# others.net
KiCad netlist of a schematic drawn in Altium Designer
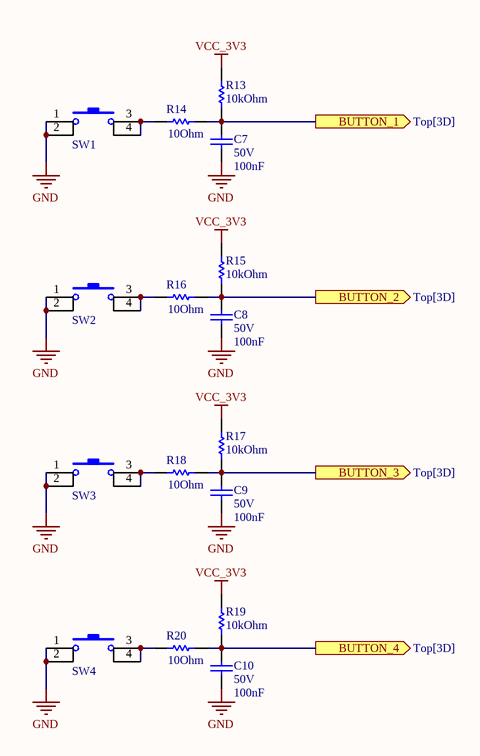
[diagram p0: others.SchDoc]

(export (version "E")
  (design (tool "Eeschema 10.0.6"))
  (components
    (comp (ref "C7")
      (value "~")
      (footprint "CAP_0603_High_density")
      (description "Generic Ceramic Capacitor SMD")
      (fields
        (field (name "TOLERANCE") "10%")
        (field (name "VOLTAGE") "50V")
        (field (name "CAPACITANCE") "100nF")
      )
      (libsource (lib "altium_conclusive_library") (part "Capacitor SMD"))
    )
    (comp (ref "C8")
      (value "~")
      (footprint "CAP_0603_High_density")
      (description "Generic Ceramic Capacitor SMD")
      (fields
        (field (name "TOLERANCE") "10%")
        (field (name "VOLTAGE") "50V")
        (field (name "CAPACITANCE") "100nF")
      )
      (libsource (lib "altium_conclusive_library") (part "Capacitor SMD"))
    )
    (comp (ref "C9")
      (value "~")
      (footprint "CAP_0603_High_density")
      (description "Generic Ceramic Capacitor SMD")
      (fields
        (field (name "TOLERANCE") "10%")
        (field (name "VOLTAGE") "50V")
        (field (name "CAPACITANCE") "100nF")
      )
      (libsource (lib "altium_conclusive_library") (part "Capacitor SMD"))
    )
    (comp (ref "C10")
      (value "~")
      (footprint "CAP_0603_High_density")
      (description "Generic Ceramic Capacitor SMD")
      (fields
        (field (name "TOLERANCE") "10%")
        (field (name "VOLTAGE") "50V")
        (field (name "CAPACITANCE") "100nF")
      )
      (libsource (lib "altium_conclusive_library") (part "Capacitor SMD"))
    )
    (comp (ref "R13")
      (value "0603 10kOhm 1%")
      (footprint "RES_0603")
      (description "Generic Resistor SMD")
      (fields (field (name "RESISTANCE") "10kOhm"))
      (libsource (lib "MY_LIB") (part "Resistor SMD_1"))
    )
    (comp (ref "R14")
      (value "0603 10Ohm 1%")
      (footprint "RES_0603")
      (description "Generic Resistor SMD")
      (fields (field (name "RESISTANCE") "10Ohm"))
      (libsource (lib "MY_LIB") (part "Resistor SMD_1"))
    )
    (comp (ref "R15")
      (value "0603 10kOhm 1%")
      (footprint "RES_0603")
      (description "Generic Resistor SMD")
      (fields (field (name "RESISTANCE") "10kOhm"))
      (libsource (lib "MY_LIB") (part "Resistor SMD_1"))
    )
    (comp (ref "R16")
      (value "0603 10Ohm 1%")
      (footprint "RES_0603")
      (description "Generic Resistor SMD")
      (fields (field (name "RESISTANCE") "10Ohm"))
      (libsource (lib "MY_LIB") (part "Resistor SMD_1"))
    )
    (comp (ref "R17")
      (value "0603 10kOhm 1%")
      (footprint "RES_0603")
      (description "Generic Resistor SMD")
      (fields (field (name "RESISTANCE") "10kOhm"))
      (libsource (lib "MY_LIB") (part "Resistor SMD_1"))
    )
    (comp (ref "R18")
      (value "0603 10Ohm 1%")
      (footprint "RES_0603")
      (description "Generic Resistor SMD")
      (fields (field (name "RESISTANCE") "10Ohm"))
      (libsource (lib "MY_LIB") (part "Resistor SMD_1"))
    )
    (comp (ref "R19")
      (value "0603 10kOhm 1%")
      (footprint "RES_0603")
      (description "Generic Resistor SMD")
      (fields (field (name "RESISTANCE") "10kOhm"))
      (libsource (lib "MY_LIB") (part "Resistor SMD_1"))
    )
    (comp (ref "R20")
      (value "0603 10Ohm 1%")
      (footprint "RES_0603")
      (description "Generic Resistor SMD")
      (fields (field (name "RESISTANCE") "10Ohm"))
      (libsource (lib "MY_LIB") (part "Resistor SMD_1"))
    )
    (comp (ref "SW1")
      (value "SWITCH SMD")
      (footprint "B3FS-1010")
      (description "SMD SWITCH B3FS-1010")
      (libsource (lib "MY_LIB") (part "B3FS-1010"))
    )
    (comp (ref "SW2")
      (value "SWITCH SMD")
      (footprint "B3FS-1010")
      (description "SMD SWITCH B3FS-1010")
      (libsource (lib "MY_LIB") (part "B3FS-1010"))
    )
    (comp (ref "SW3")
      (value "SWITCH SMD")
      (footprint "B3FS-1010")
      (description "SMD SWITCH B3FS-1010")
      (libsource (lib "MY_LIB") (part "B3FS-1010"))
    )
    (comp (ref "SW4")
      (value "SWITCH SMD")
      (footprint "B3FS-1010")
      (description "SMD SWITCH B3FS-1010")
      (libsource (lib "MY_LIB") (part "B3FS-1010"))
    )
  )
  (nets
    (net (code "1") (name "/BUTTON_1") (class "Default")
      (node (ref "C7") (pin "1") (pinfunction "1_1") (pintype "passive"))
      (node (ref "R13") (pin "2") (pinfunction "2_2") (pintype "passive"))
      (node (ref "R14") (pin "2") (pinfunction "2_2") (pintype "passive"))
    )
    (net (code "2") (name "/BUTTON_2") (class "Default")
      (node (ref "C8") (pin "1") (pinfunction "1_1") (pintype "passive"))
      (node (ref "R15") (pin "2") (pinfunction "2_2") (pintype "passive"))
      (node (ref "R16") (pin "2") (pinfunction "2_2") (pintype "passive"))
    )
    (net (code "3") (name "/BUTTON_3") (class "Default")
      (node (ref "C9") (pin "1") (pinfunction "1_1") (pintype "passive"))
      (node (ref "R17") (pin "2") (pinfunction "2_2") (pintype "passive"))
      (node (ref "R18") (pin "2") (pinfunction "2_2") (pintype "passive"))
    )
    (net (code "4") (name "/BUTTON_4") (class "Default")
      (node (ref "C10") (pin "1") (pinfunction "1_1") (pintype "passive"))
      (node (ref "R19") (pin "2") (pinfunction "2_2") (pintype "passive"))
      (node (ref "R20") (pin "2") (pinfunction "2_2") (pintype "passive"))
    )
    (net (code "5") (name "GND") (class "Default")
      (node (ref "C10") (pin "2") (pinfunction "2_2") (pintype "passive"))
      (node (ref "C7") (pin "2") (pinfunction "2_2") (pintype "passive"))
      (node (ref "C8") (pin "2") (pinfunction "2_2") (pintype "passive"))
      (node (ref "C9") (pin "2") (pinfunction "2_2") (pintype "passive"))
      (node (ref "SW1") (pin "1") (pinfunction "1_1") (pintype "passive"))
      (node (ref "SW1") (pin "2") (pinfunction "2_2") (pintype "passive"))
      (node (ref "SW2") (pin "1") (pinfunction "1_1") (pintype "passive"))
      (node (ref "SW2") (pin "2") (pinfunction "2_2") (pintype "passive"))
      (node (ref "SW3") (pin "1") (pinfunction "1_1") (pintype "passive"))
      (node (ref "SW3") (pin "2") (pinfunction "2_2") (pintype "passive"))
      (node (ref "SW4") (pin "1") (pinfunction "1_1") (pintype "passive"))
      (node (ref "SW4") (pin "2") (pinfunction "2_2") (pintype "passive"))
    )
    (net (code "6") (name "Net-(R14-Pad1)") (class "Default")
      (node (ref "R14") (pin "1") (pinfunction "1_1") (pintype "passive"))
      (node (ref "SW1") (pin "3") (pinfunction "3_3") (pintype "passive"))
      (node (ref "SW1") (pin "4") (pinfunction "4_4") (pintype "passive"))
    )
    (net (code "7") (name "Net-(R16-Pad1)") (class "Default")
      (node (ref "R16") (pin "1") (pinfunction "1_1") (pintype "passive"))
      (node (ref "SW2") (pin "3") (pinfunction "3_3") (pintype "passive"))
      (node (ref "SW2") (pin "4") (pinfunction "4_4") (pintype "passive"))
    )
    (net (code "8") (name "Net-(R18-Pad1)") (class "Default")
      (node (ref "R18") (pin "1") (pinfunction "1_1") (pintype "passive"))
      (node (ref "SW3") (pin "3") (pinfunction "3_3") (pintype "passive"))
      (node (ref "SW3") (pin "4") (pinfunction "4_4") (pintype "passive"))
    )
    (net (code "9") (name "Net-(R20-Pad1)") (class "Default")
      (node (ref "R20") (pin "1") (pinfunction "1_1") (pintype "passive"))
      (node (ref "SW4") (pin "3") (pinfunction "3_3") (pintype "passive"))
      (node (ref "SW4") (pin "4") (pinfunction "4_4") (pintype "passive"))
    )
    (net (code "10") (name "VCC_3V3") (class "Default")
      (node (ref "R13") (pin "1") (pinfunction "1_1") (pintype "passive"))
      (node (ref "R15") (pin "1") (pinfunction "1_1") (pintype "passive"))
      (node (ref "R17") (pin "1") (pinfunction "1_1") (pintype "passive"))
      (node (ref "R19") (pin "1") (pinfunction "1_1") (pintype "passive"))
    )
  )
)
